# CoolRoof_Terminal_Module_alimentation.net
KiCad netlist of a schematic drawn in EAGLE
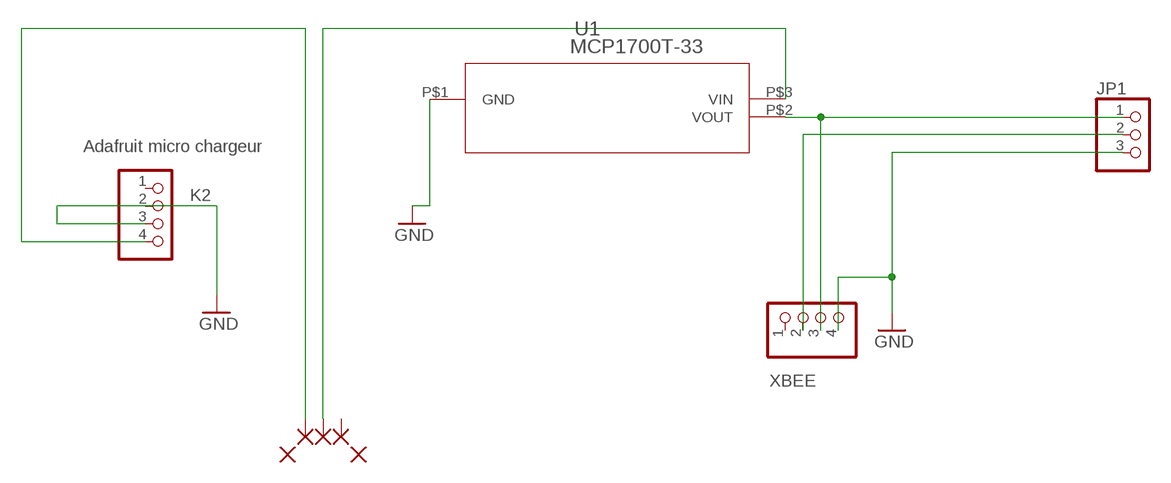
[diagram p0: schematic, sheet 1]

(export (version "E")
  (design (tool "Eeschema 10.0.6"))
  (components
    (comp (ref "JP1")
      (value "PINHD-1X3")
      (footprint "eagle-import:1X03")
      (libsource (lib "eagle-import") (part "PINHD-1X3"))
    )
    (comp (ref "K2")
      (value "Adafruit micro chargeur")
      (footprint "eagle-import:1X04")
      (libsource (lib "eagle-import") (part "pinhead_325_PINHD-1X4"))
    )
    (comp (ref "PAD1")
      (value "1,6/0,8")
      (footprint "eagle-import:1,6_0,8")
      (libsource (lib "eagle-import") (part "1,6/0,8"))
    )
    (comp (ref "PAD2")
      (value "1,6/0,8")
      (footprint "eagle-import:1,6_0,8")
      (libsource (lib "eagle-import") (part "1,6/0,8"))
    )
    (comp (ref "PAD3")
      (value "1,6/0,8")
      (footprint "eagle-import:1,6_0,8")
      (libsource (lib "eagle-import") (part "1,6/0,8"))
    )
    (comp (ref "PAD4")
      (value "N_2,0/1,5")
      (footprint "eagle-import:2,0_1,5")
      (libsource (lib "eagle-import") (part "N_2,0/1,5"))
    )
    (comp (ref "PAD5")
      (value "N_2,0/1,5")
      (footprint "eagle-import:2,0_1,5")
      (libsource (lib "eagle-import") (part "N_2,0/1,5"))
    )
    (comp (ref "U1")
      (value "MCP1700T-33")
      (footprint "eagle-import:SOT-23")
      (libsource (lib "eagle-import") (part "MCP1700T-3302E/TTSOT-23"))
    )
    (comp (ref "XBEE")
      (value "PINHD-1X4")
      (footprint "eagle-import:1X04")
      (libsource (lib "eagle-import") (part "PINHD-1X4"))
    )
  )
  (nets
    (net (code "1") (name "GND") (class "Default")
      (node (ref "JP1") (pin "3") (pinfunction "3_3") (pintype "passive"))
      (node (ref "K2") (pin "2") (pinfunction "2_2") (pintype "passive"))
      (node (ref "K2") (pin "3") (pinfunction "3_3") (pintype "passive"))
      (node (ref "U1") (pin "P$1") (pinfunction "GND_P$1") (pintype "passive"))
      (node (ref "XBEE") (pin "4") (pinfunction "4_4") (pintype "passive"))
    )
    (net (code "2") (name "Net-(JP1-Pad2)") (class "Default")
      (node (ref "JP1") (pin "2") (pinfunction "2_2") (pintype "passive"))
      (node (ref "XBEE") (pin "2") (pinfunction "2_2") (pintype "passive"))
    )
    (net (code "3") (name "Net-(PAD1-P)") (class "Default")
      (node (ref "K2") (pin "4") (pinfunction "4_4") (pintype "passive"))
      (node (ref "PAD1") (pin "1") (pinfunction "P_1") (pintype "passive"))
    )
    (net (code "4") (name "Net-(PAD2-P)") (class "Default")
      (node (ref "PAD2") (pin "1") (pinfunction "P_1") (pintype "passive"))
      (node (ref "U1") (pin "P$3") (pinfunction "VIN_P$3") (pintype "passive"))
    )
    (net (code "5") (name "Net-(U1-VOUT)") (class "Default")
      (node (ref "JP1") (pin "1") (pinfunction "1_1") (pintype "passive"))
      (node (ref "U1") (pin "P$2") (pinfunction "VOUT_P$2") (pintype "passive"))
      (node (ref "XBEE") (pin "3") (pinfunction "3_3") (pintype "passive"))
    )
    (net (code "6") (name "unconnected-(K2-Pad1)") (class "Default")
      (node (ref "K2") (pin "1") (pinfunction "1_1") (pintype "passive"))
    )
    (net (code "7") (name "unconnected-(PAD3-P-Pad1)") (class "Default")
      (node (ref "PAD3") (pin "1") (pinfunction "P_1") (pintype "passive"))
    )
    (net (code "8") (name "unconnected-(XBEE-Pad1)") (class "Default")
      (node (ref "XBEE") (pin "1") (pinfunction "1_1") (pintype "passive"))
    )
  )
)
